# fanmonitor.net
KiCad netlist of a schematic drawn in EAGLE
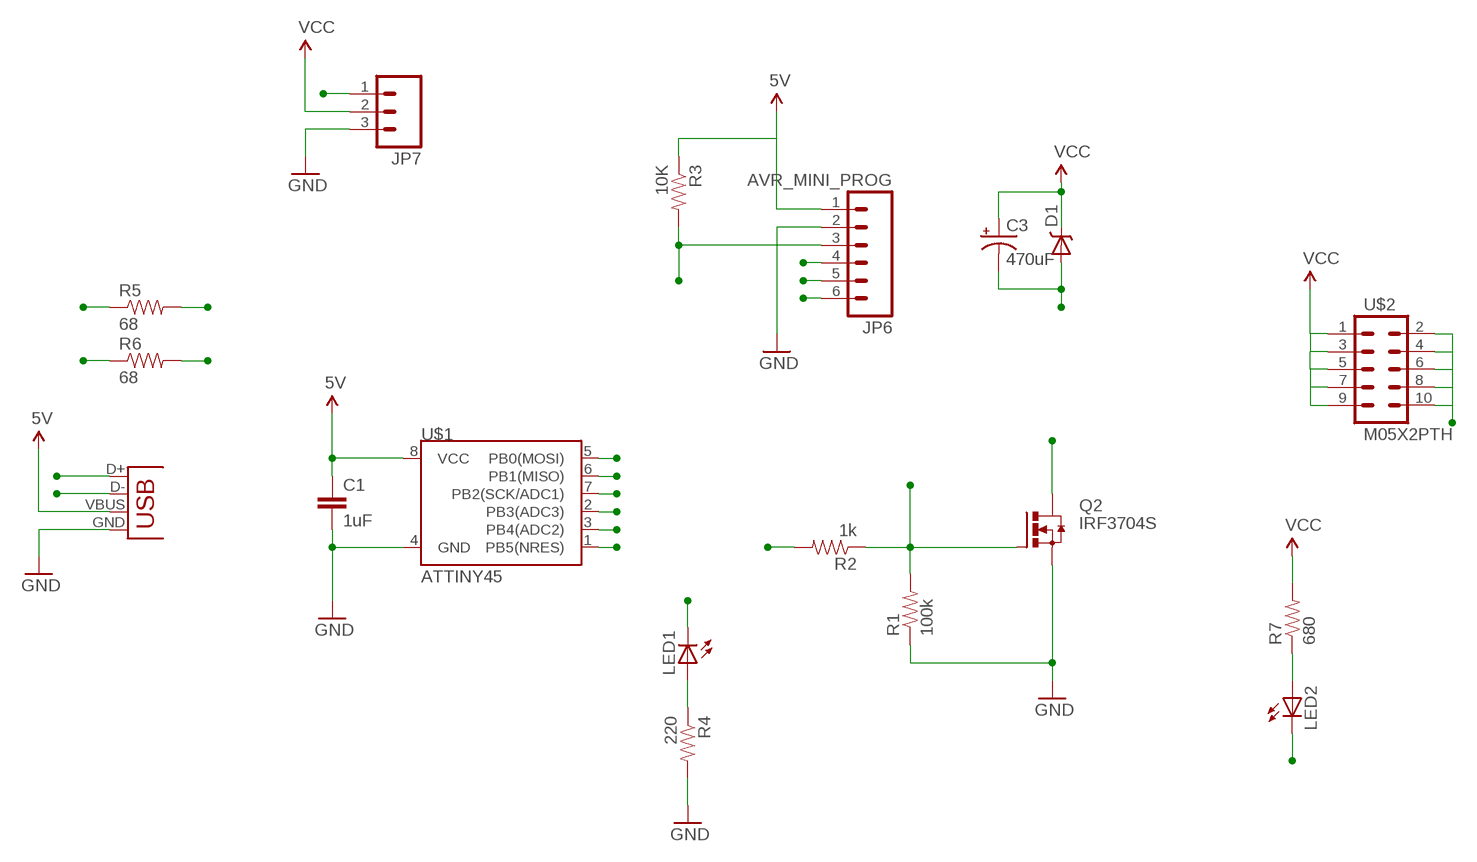
[diagram p0: schematic, sheet 1]

(export (version "E")
  (design (tool "Eeschema 10.0.6"))
  (components
    (comp (ref "C1")
      (value "1uF")
      (footprint "eagle-import:0603-CAP")
      (libsource (lib "eagle-import") (part "CAP0603-CAP"))
    )
    (comp (ref "C3")
      (value "470uF")
      (footprint "eagle-import:PANASONIC_D")
      (libsource (lib "eagle-import") (part "CAP_POLD"))
    )
    (comp (ref "D1")
      (value "DIODE-SCHOTTKY_")
      (footprint "eagle-import:SMA-DIODE")
      (libsource (lib "eagle-import") (part "DIODE-SCHOTTKY_"))
    )
    (comp (ref "JP6")
      (value "AVR_MINI_PROG")
      (footprint "eagle-import:1X06")
      (libsource (lib "eagle-import") (part "M06SIP"))
    )
    (comp (ref "JP7")
      (value "M03PTH")
      (footprint "eagle-import:1X03")
      (libsource (lib "eagle-import") (part "M03PTH"))
    )
    (comp (ref "LED1")
      (value "LED0603")
      (footprint "eagle-import:LED-0603")
      (libsource (lib "eagle-import") (part "LED0603"))
    )
    (comp (ref "LED2")
      (value "LED0603")
      (footprint "eagle-import:LED-0603")
      (libsource (lib "eagle-import") (part "LED0603"))
    )
    (comp (ref "Q2")
      (value "IRF3704S")
      (footprint "eagle-import:D2PACK")
      (libsource (lib "eagle-import") (part "IRF3704S"))
    )
    (comp (ref "R1")
      (value "100k")
      (footprint "eagle-import:0603-RES")
      (libsource (lib "eagle-import") (part "RESISTOR0603-RES"))
    )
    (comp (ref "R2")
      (value "1k")
      (footprint "eagle-import:0603-RES")
      (libsource (lib "eagle-import") (part "RESISTOR0603-RES"))
    )
    (comp (ref "R3")
      (value "10K")
      (footprint "eagle-import:0603-RES")
      (libsource (lib "eagle-import") (part "RESISTOR0603-RES"))
    )
    (comp (ref "R4")
      (value "220")
      (footprint "eagle-import:0603-RES")
      (libsource (lib "eagle-import") (part "RESISTOR0603-RES"))
    )
    (comp (ref "R5")
      (value "68")
      (footprint "eagle-import:0603-RES")
      (libsource (lib "eagle-import") (part "RESISTOR0603-RES"))
    )
    (comp (ref "R6")
      (value "68")
      (footprint "eagle-import:0603-RES")
      (libsource (lib "eagle-import") (part "RESISTOR0603-RES"))
    )
    (comp (ref "R7")
      (value "680")
      (footprint "eagle-import:0603-RES")
      (libsource (lib "eagle-import") (part "RESISTOR0603-RES"))
    )
    (comp (ref "U$1")
      (value "ATTINY45")
      (footprint "eagle-import:SO08-EIAJ")
      (libsource (lib "eagle-import") (part "ATTINY45"))
    )
    (comp (ref "U$2")
      (value "M05X2PTH")
      (footprint "eagle-import:AVR_ICSP")
      (libsource (lib "eagle-import") (part "M05X2PTH"))
    )
    (comp (ref "X1")
      (value "USBSMD")
      (footprint "eagle-import:USB-MINIB")
      (libsource (lib "eagle-import") (part "USBSMD"))
    )
  )
  (nets
    (net (code "1") (name "/D+") (class "Default")
      (node (ref "R5") (pin "1") (pinfunction "1_1") (pintype "passive"))
      (node (ref "X1") (pin "D+") (pinfunction "D+_D+") (pintype "bidirectional"))
    )
    (net (code "2") (name "/D-") (class "Default")
      (node (ref "R6") (pin "1") (pinfunction "1_1") (pintype "passive"))
      (node (ref "X1") (pin "D-") (pinfunction "D-_D-") (pintype "bidirectional"))
    )
    (net (code "3") (name "/MISO") (class "Default")
      (node (ref "JP6") (pin "6") (pinfunction "6_6") (pintype "passive"))
      (node (ref "R6") (pin "2") (pinfunction "2_2") (pintype "passive"))
      (node (ref "U$1") (pin "6") (pinfunction "PB1(MISO)_6") (pintype "bidirectional"))
    )
    (net (code "4") (name "/MOSI") (class "Default")
      (node (ref "JP6") (pin "4") (pinfunction "4_4") (pintype "passive"))
      (node (ref "R5") (pin "2") (pinfunction "2_2") (pintype "passive"))
      (node (ref "U$1") (pin "5") (pinfunction "PB0(MOSI)_5") (pintype "bidirectional"))
    )
    (net (code "5") (name "/PWM") (class "Default")
      (node (ref "R2") (pin "2") (pinfunction "2_2") (pintype "passive"))
      (node (ref "U$1") (pin "2") (pinfunction "PB3(ADC3)_2") (pintype "bidirectional"))
    )
    (net (code "6") (name "/PWM_OUT") (class "Default")
      (node (ref "C3") (pin "-") (pinfunction "-_-") (pintype "passive"))
      (node (ref "D1") (pin "A") (pinfunction "A_A") (pintype "passive"))
      (node (ref "LED2") (pin "C") (pinfunction "C_C") (pintype "passive"))
      (node (ref "Q2") (pin "2") (pinfunction "D_2") (pintype "passive"))
      (node (ref "U$2") (pin "10") (pinfunction "10_10") (pintype "passive"))
      (node (ref "U$2") (pin "2") (pinfunction "2_2") (pintype "passive"))
      (node (ref "U$2") (pin "4") (pinfunction "4_4") (pintype "passive"))
      (node (ref "U$2") (pin "6") (pinfunction "6_6") (pintype "passive"))
      (node (ref "U$2") (pin "8") (pinfunction "8_8") (pintype "passive"))
    )
    (net (code "7") (name "/SCK") (class "Default")
      (node (ref "JP6") (pin "5") (pinfunction "5_5") (pintype "passive"))
      (node (ref "U$1") (pin "7") (pinfunction "PB2(SCK/ADC1)_7") (pintype "bidirectional"))
    )
    (net (code "8") (name "/SPD") (class "Default")
      (node (ref "JP7") (pin "1") (pinfunction "1_1") (pintype "passive"))
      (node (ref "Q2") (pin "1") (pinfunction "G_1") (pintype "passive"))
      (node (ref "R1") (pin "2") (pinfunction "2_2") (pintype "passive"))
      (node (ref "R2") (pin "1") (pinfunction "1_1") (pintype "passive"))
    )
    (net (code "9") (name "/STAT") (class "Default")
      (node (ref "LED1") (pin "C") (pinfunction "C_C") (pintype "passive"))
      (node (ref "U$1") (pin "3") (pinfunction "PB4(ADC2)_3") (pintype "bidirectional"))
    )
    (net (code "10") (name "/{slash}RST") (class "Default")
      (node (ref "JP6") (pin "3") (pinfunction "3_3") (pintype "passive"))
      (node (ref "R3") (pin "2") (pinfunction "2_2") (pintype "passive"))
      (node (ref "U$1") (pin "1") (pinfunction "PB5(NRES)_1") (pintype "bidirectional"))
    )
    (net (code "11") (name "5V") (class "Default")
      (node (ref "C1") (pin "1") (pinfunction "1_1") (pintype "passive"))
      (node (ref "JP6") (pin "1") (pinfunction "1_1") (pintype "passive"))
      (node (ref "R3") (pin "1") (pinfunction "1_1") (pintype "passive"))
      (node (ref "U$1") (pin "8") (pinfunction "VCC_8") (pintype "bidirectional"))
      (node (ref "X1") (pin "VBUS") (pinfunction "VBUS_VBUS") (pintype "bidirectional"))
    )
    (net (code "12") (name "GND") (class "Default")
      (node (ref "C1") (pin "2") (pinfunction "2_2") (pintype "passive"))
      (node (ref "JP6") (pin "2") (pinfunction "2_2") (pintype "passive"))
      (node (ref "JP7") (pin "3") (pinfunction "3_3") (pintype "passive"))
      (node (ref "Q2") (pin "3") (pinfunction "S_3") (pintype "passive"))
      (node (ref "R1") (pin "1") (pinfunction "1_1") (pintype "passive"))
      (node (ref "R4") (pin "2") (pinfunction "2_2") (pintype "passive"))
      (node (ref "U$1") (pin "4") (pinfunction "GND_4") (pintype "bidirectional"))
      (node (ref "X1") (pin "GND") (pinfunction "GND_GND") (pintype "bidirectional"))
    )
    (net (code "13") (name "Net-(LED1-PadA)") (class "Default")
      (node (ref "LED1") (pin "A") (pinfunction "A_A") (pintype "passive"))
      (node (ref "R4") (pin "1") (pinfunction "1_1") (pintype "passive"))
    )
    (net (code "14") (name "Net-(LED2-PadA)") (class "Default")
      (node (ref "LED2") (pin "A") (pinfunction "A_A") (pintype "passive"))
      (node (ref "R7") (pin "1") (pinfunction "1_1") (pintype "passive"))
    )
    (net (code "15") (name "VCC") (class "Default")
      (node (ref "C3") (pin "+") (pinfunction "+_+") (pintype "passive"))
      (node (ref "D1") (pin "C") (pinfunction "C_C") (pintype "passive"))
      (node (ref "JP7") (pin "2") (pinfunction "2_2") (pintype "passive"))
      (node (ref "R7") (pin "2") (pinfunction "2_2") (pintype "passive"))
      (node (ref "U$2") (pin "1") (pinfunction "1_1") (pintype "passive"))
      (node (ref "U$2") (pin "3") (pinfunction "3_3") (pintype "passive"))
      (node (ref "U$2") (pin "5") (pinfunction "5_5") (pintype "passive"))
      (node (ref "U$2") (pin "7") (pinfunction "7_7") (pintype "passive"))
      (node (ref "U$2") (pin "9") (pinfunction "9_9") (pintype "passive"))
    )
  )
)
